# STM32_-_MCU.net
KiCad netlist of a schematic drawn in Altium Designer
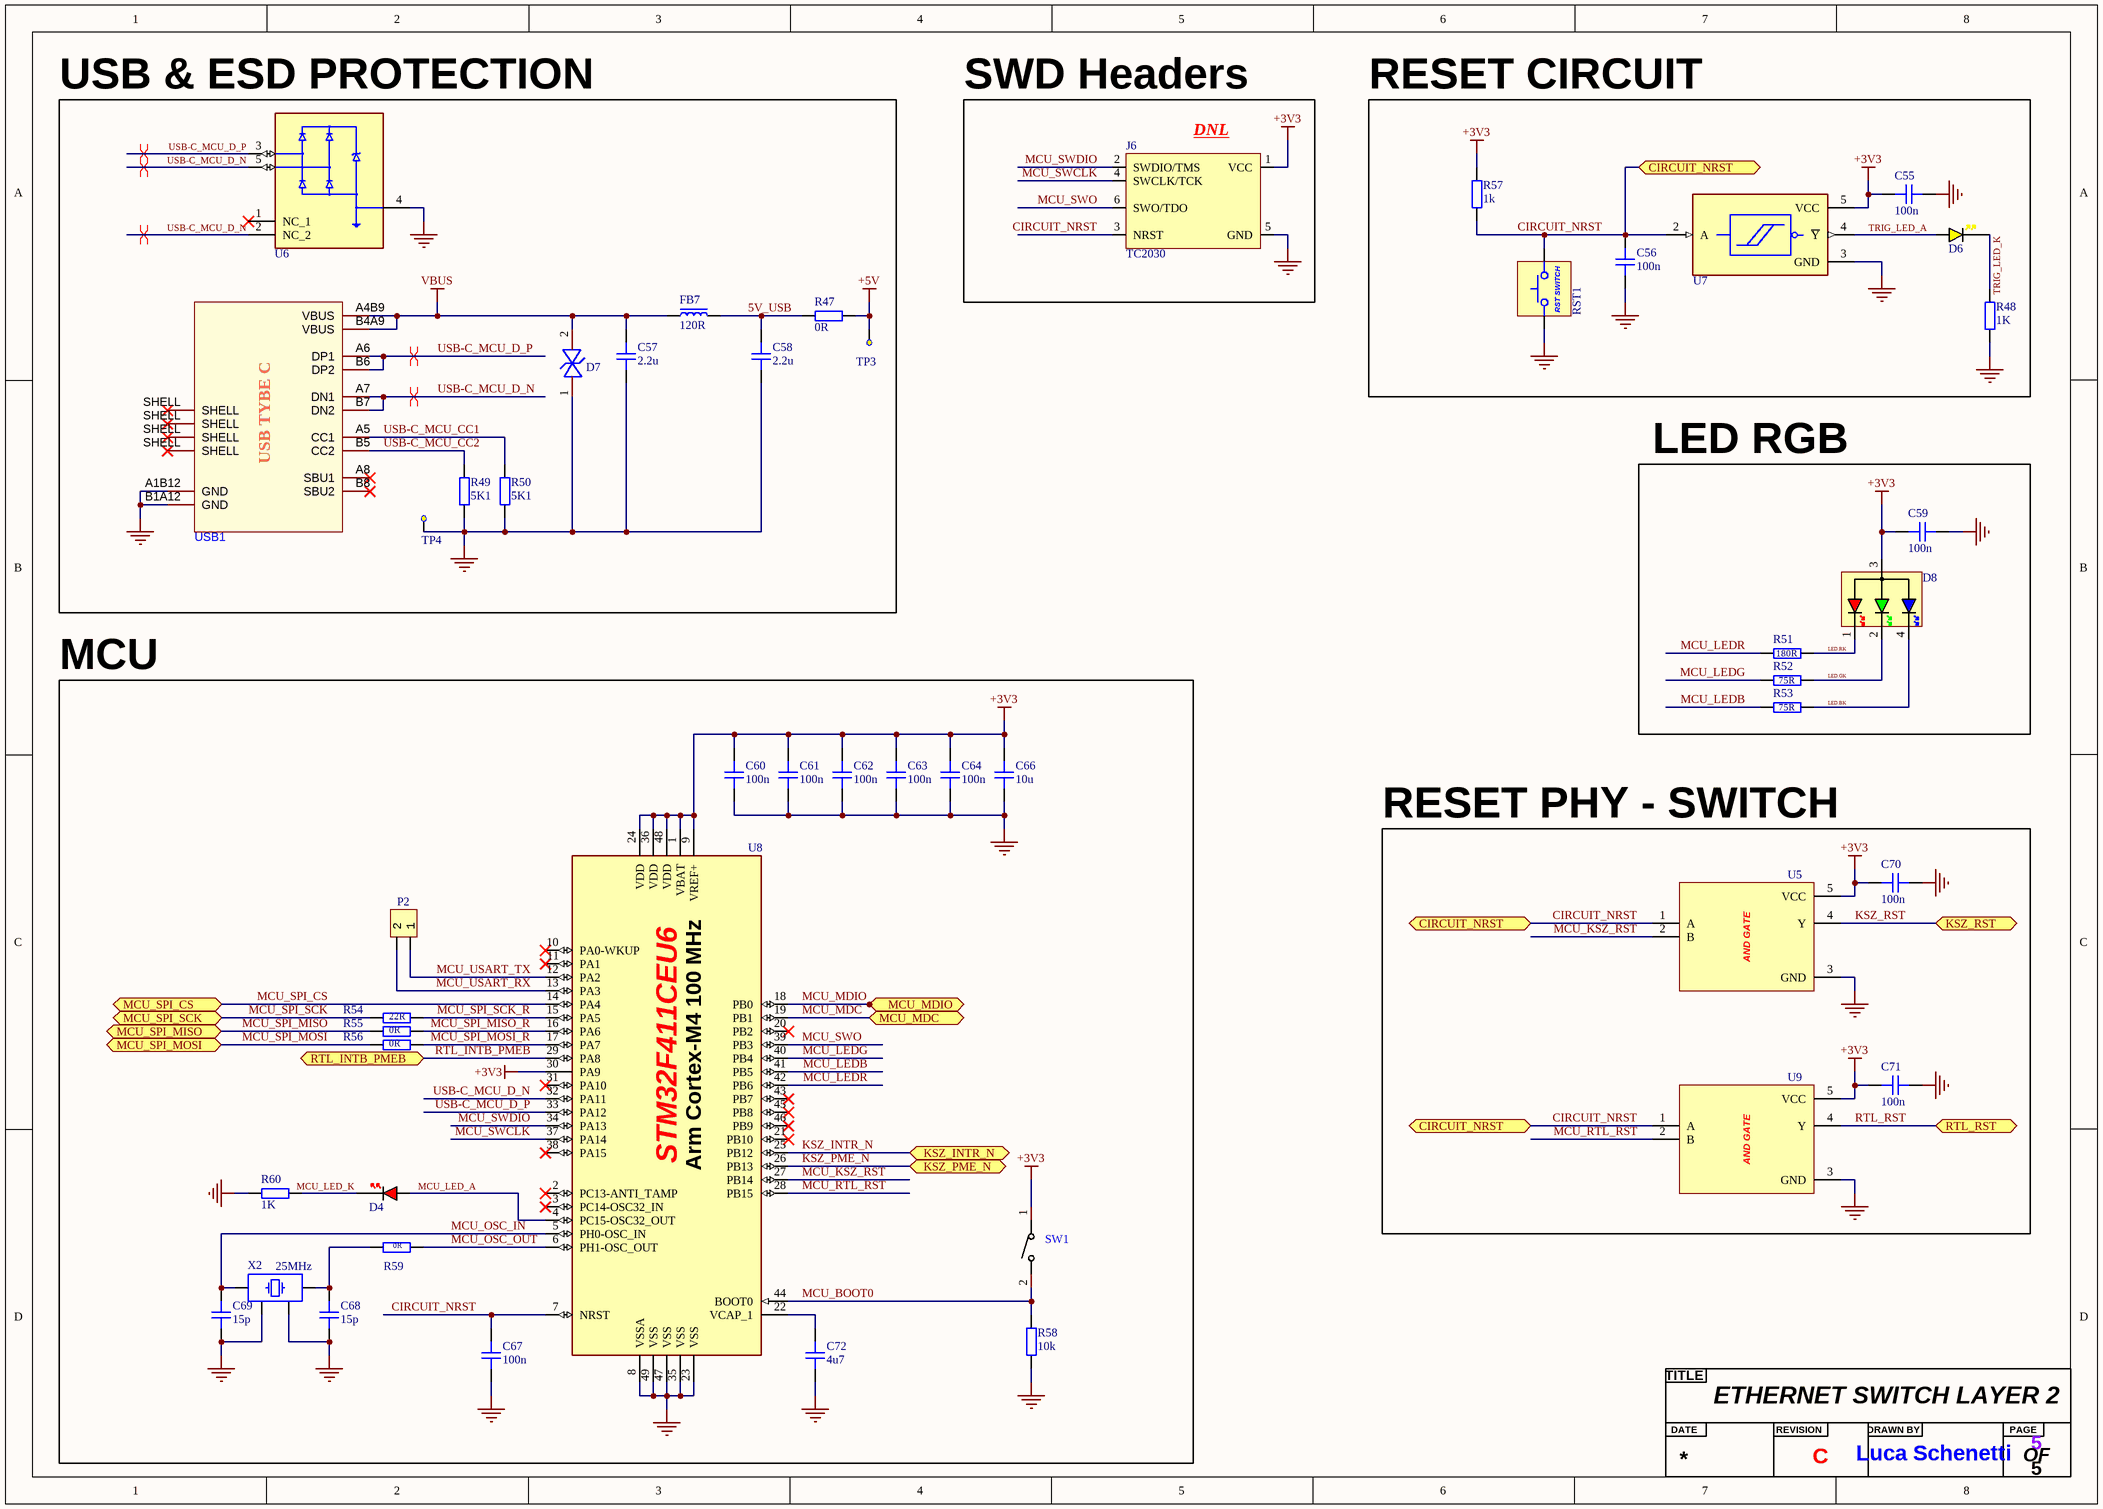
[diagram p0: STM32 - MCU.SchDoc]

(export (version "E")
  (design (tool "Eeschema 10.0.6"))
  (components
    (comp (ref "C55")
      (value "100n")
      (footprint "CAP_0402")
      (description "Capacitor SMD 0402 [C1525]")
      (libsource (lib "Schematic-Lib-PhilsLab") (part "CAP_0402"))
    )
    (comp (ref "C56")
      (value "100n")
      (footprint "CAP_0402")
      (description "Capacitor SMD 0402 [C1525]")
      (libsource (lib "Schematic-Lib-PhilsLab") (part "CAP_0402"))
    )
    (comp (ref "C57")
      (value "2.2u")
      (footprint "CAP_0603")
      (description "Capacitor SMD 0603 [C23630]")
      (libsource (lib "Schematic-Lib-PhilsLab") (part "CAP_0603"))
    )
    (comp (ref "C58")
      (value "2.2u")
      (footprint "CAP_0603")
      (description "Capacitor SMD 0603 [C23630]")
      (libsource (lib "Schematic-Lib-PhilsLab") (part "CAP_0603"))
    )
    (comp (ref "C59")
      (value "100n")
      (footprint "CAP_0402")
      (description "Capacitor SMD 0402 [C1525]")
      (libsource (lib "Schematic-Lib-PhilsLab") (part "CAP_0402"))
    )
    (comp (ref "C60")
      (value "100n")
      (footprint "CAP_0603")
      (description "Capacitor SMD 0603 [C14663]")
      (libsource (lib "Schematic-Lib-PhilsLab") (part "CAP_0603"))
    )
    (comp (ref "C61")
      (value "100n")
      (footprint "CAP_0603")
      (description "Capacitor SMD 0603 [C14663]")
      (libsource (lib "Schematic-Lib-PhilsLab") (part "CAP_0603"))
    )
    (comp (ref "C62")
      (value "100n")
      (footprint "CAP_0603")
      (description "Capacitor SMD 0603 [C14663]")
      (libsource (lib "Schematic-Lib-PhilsLab") (part "CAP_0603"))
    )
    (comp (ref "C63")
      (value "100n")
      (footprint "CAP_0603")
      (description "Capacitor SMD 0603 [C14663]")
      (libsource (lib "Schematic-Lib-PhilsLab") (part "CAP_0603"))
    )
    (comp (ref "C64")
      (value "100n")
      (footprint "CAP_0603")
      (description "Capacitor SMD 0603 [C14663]")
      (libsource (lib "Schematic-Lib-PhilsLab") (part "CAP_0603"))
    )
    (comp (ref "C66")
      (value "10u")
      (footprint "CAP_0603")
      (description "Capacitor SMD 0603 [C96446]")
      (libsource (lib "Schematic-Lib-PhilsLab") (part "CAP_0603"))
    )
    (comp (ref "C67")
      (value "100n")
      (footprint "CAP_0603")
      (description "Capacitor SMD 0603 [C14663]")
      (libsource (lib "Schematic-Lib-PhilsLab") (part "CAP_0603"))
    )
    (comp (ref "C68")
      (value "15p")
      (footprint "CAP_0402")
      (description "Capacitor SMD 0402 [C1548]")
      (libsource (lib "Schematic-Lib-PhilsLab") (part "CAP_0402"))
    )
    (comp (ref "C69")
      (value "15p")
      (footprint "CAP_0402")
      (description "Capacitor SMD 0402 [C1548]")
      (libsource (lib "Schematic-Lib-PhilsLab") (part "CAP_0402"))
    )
    (comp (ref "C70")
      (value "100n")
      (footprint "CAP_0402")
      (description "Capacitor SMD 0402 [C1525]")
      (libsource (lib "Schematic-Lib-PhilsLab") (part "CAP_0402"))
    )
    (comp (ref "C71")
      (value "100n")
      (footprint "CAP_0402")
      (description "Capacitor SMD 0402 [C1525]")
      (libsource (lib "Schematic-Lib-PhilsLab") (part "CAP_0402"))
    )
    (comp (ref "C72")
      (value "4u7")
      (footprint "CAP_0603")
      (description "Capacitor SMD 0603 [C19666]")
      (libsource (lib "Schematic-Lib-PhilsLab") (part "CAP_0603"))
    )
    (comp (ref "D4")
      (value "RED")
      (footprint "LED_0603_RED")
      (description "LED 0603 RED SMD[C2926776]")
      (libsource (lib "Schematic-Lib-PhilsLab") (part "LED_0603_RED"))
    )
    (comp (ref "D6")
      (value "YELLOW")
      (footprint "LED_0603_YELLOW")
      (description "LED 0603 YELLOW SMD[C72038]")
      (libsource (lib "Schematic-Lib-PhilsLab") (part "LED_0603_YELLOW"))
    )
    (comp (ref "D7")
      (value "ESD Protection TVS 6.0V")
      (footprint "SMF6.0CA")
      (description "[C2990473]")
      (libsource (lib "My_Library") (part "SMF6.0CA"))
    )
    (comp (ref "D8")
      (value "RGB_LED")
      (footprint "XL-2012RGBC")
      (description "[C965848]")
      (libsource (lib "My_Library") (part "RGB_LED_0805"))
    )
    (comp (ref "FB7")
      (value "120R")
      (footprint "FB_0603")
      (description "Ferrite Bead SMD 0603[C76892]")
      (libsource (lib "Schematic-Lib-PhilsLab") (part "FB_0603"))
    )
    (comp (ref "J6")
      (value "TC2030")
      (footprint "TC2030-FP")
      (description "Tag-Connect No-Solder SWD Debug Connector DO NOT PLACE")
      (fields (field (name "MANUFACTURER") "Tag-Connect"))
      (libsource (lib "Schematic-Lib-PhilsLab") (part "TC2030"))
    )
    (comp (ref "P2")
      (value "HDR1x2")
      (footprint "PCB_ConnectorHDR:HDR1X2_2.54_180")
      (description "Header")
      (libsource (lib "SCH_ConnectorHDR") (part "HDR1x2_2.54T"))
    )
    (comp (ref "R47")
      (value "0R")
      (footprint "RES_0603")
      (description "[C21189]")
      (libsource (lib "Schematic-Lib-PhilsLab") (part "RES_0603"))
    )
    (comp (ref "R48")
      (value "1K")
      (footprint "RES_0402")
      (description "Resistor SMD 0402 [C11702]")
      (libsource (lib "Schematic-Lib-PhilsLab") (part "RES_0402"))
    )
    (comp (ref "R49")
      (value "5K1")
      (footprint "RES_0603")
      (description "[C23186]")
      (libsource (lib "Schematic-Lib-PhilsLab") (part "RES_0603"))
    )
    (comp (ref "R50")
      (value "5K1")
      (footprint "RES_0603")
      (description "[C23186]")
      (libsource (lib "Schematic-Lib-PhilsLab") (part "RES_0603"))
    )
    (comp (ref "R51")
      (value "180R")
      (footprint "RES_0603")
      (description "[C22828]")
      (libsource (lib "Schematic-Lib-PhilsLab") (part "RES_0603"))
    )
    (comp (ref "R52")
      (value "75R")
      (footprint "RES_0603")
      (description "[C4275]")
      (libsource (lib "Schematic-Lib-PhilsLab") (part "RES_0603"))
    )
    (comp (ref "R53")
      (value "75R")
      (footprint "RES_0603")
      (description "[C4275]")
      (libsource (lib "Schematic-Lib-PhilsLab") (part "RES_0603"))
    )
    (comp (ref "R54")
      (value "22R")
      (footprint "RES_0402")
      (description "Resistor SMD 0402 [C25092]")
      (libsource (lib "Schematic-Lib-PhilsLab") (part "RES_0402"))
    )
    (comp (ref "R55")
      (value "0R")
      (footprint "RES_0402")
      (description "Resistor SMD 0402 [C17168]")
      (libsource (lib "Schematic-Lib-PhilsLab") (part "RES_0402"))
    )
    (comp (ref "R56")
      (value "0R")
      (footprint "RES_0402")
      (description "Resistor SMD 0402 [C17168]")
      (libsource (lib "Schematic-Lib-PhilsLab") (part "RES_0402"))
    )
    (comp (ref "R57")
      (value "1k")
      (footprint "RES_0402")
      (description "Resistor SMD 0402 [C11702]")
      (libsource (lib "Schematic-Lib-PhilsLab") (part "RES_0402"))
    )
    (comp (ref "R58")
      (value "10k")
      (footprint "RES_0603")
      (description "Resistor SMD 0603[C25804]")
      (libsource (lib "Schematic-Lib-PhilsLab") (part "RES_0603"))
    )
    (comp (ref "R59")
      (value "0R")
      (footprint "RES_0402")
      (description "Resistor SMD 0402 [C17168]")
      (libsource (lib "Schematic-Lib-PhilsLab") (part "RES_0402"))
    )
    (comp (ref "R60")
      (value "1K")
      (footprint "RES_0402")
      (description "Resistor SMD 0402 [C11702]")
      (libsource (lib "Schematic-Lib-PhilsLab") (part "RES_0402"))
    )
    (comp (ref "RST1")
      (value "RST_SWITCH_STM32")
      (footprint "RST_SWITCH")
      (description "[C720477]")
      (libsource (lib "My_Library") (part "RST_SWITCH"))
    )
    (comp (ref "SW1")
      (value "TS-1088-AR02016")
      (footprint "TS-1088-AR02016")
      (description "[C720477]")
      (fields (field (name "MANUFACTURER") "XUNPU(讯普)"))
      (libsource (lib "My_Library") (part "TS-1088-AR02016"))
    )
    (comp (ref "TP3")
      (value "Test Point")
      (footprint "Test Point")
      (libsource (lib "My_Library") (part "Test Point"))
    )
    (comp (ref "TP4")
      (value "Test Point")
      (footprint "Test Point")
      (libsource (lib "My_Library") (part "Test Point"))
    )
    (comp (ref "U5")
      (value "AND GATE")
      (footprint "SN74LVC1G08DBVR")
      (description "[C7666]")
      (libsource (lib "My_Library") (part "SN74LVC1G08DBVR"))
    )
    (comp (ref "U6")
      (value "TVS USB 2.0 ±25-kV")
      (footprint "TPD2E2U06DRLR")
      (description "[C1972959]")
      (libsource (lib "My_Library") (part "TPD2E2U06DRLR"))
    )
    (comp (ref "U7")
      (value "Schmitt Trigger 1.65V~5.5V")
      (footprint "74LVC1G14GW,125")
      (description "[C265125]")
      (libsource (lib "My_Library") (part "74LVC1G14GW,125"))
    )
    (comp (ref "U8")
      (value "ARM® Cortex®-M4 STM32F4")
      (footprint "STM32F411CEU6")
      (description "[C60420]")
      (libsource (lib "My_Library") (part "STM32F411CEU6"))
    )
    (comp (ref "U9")
      (value "AND GATE")
      (footprint "SN74LVC1G08DBVR")
      (description "[C7666]")
      (libsource (lib "My_Library") (part "SN74LVC1G08DBVR"))
    )
    (comp (ref "USB1")
      (value "USB-C CONNECTOR")
      (footprint "USB-3.1-SMD_U262-161N-4BVC11")
      (description "[C319148]")
      (fields
        (field (name "MANUFACTURER") "XKB Connectivity(中国星坤)")
        (field (name "MANUFACTURER PART") "U262-161N-4BVC11")
      )
      (libsource (lib "My_Library") (part "U262-161N-4BVC11"))
    )
    (comp (ref "X2")
      (value "25MHz")
      (footprint "XTAL_3225")
      (description "Crystal SMD 24MHz 10PPM 7pF 3225 [C9006]")
      (fields
        (field (name "MANUFACTURER") "Epson")
        (field (name "MANUFACTURER PART NUMBER") "TSX-3225 24.0000MF15X-AC")
      )
      (libsource (lib "Schematic-Lib-PhilsLab") (part "TSX-3225_24.0000MF15X-AC"))
    )
  )
  (nets
    (net (code "1") (name "+3V3") (class "Default")
      (node (ref "C55") (pin "2") (pinfunction "2_2") (pintype "passive"))
      (node (ref "C59") (pin "2") (pinfunction "2_2") (pintype "passive"))
      (node (ref "C60") (pin "2") (pinfunction "2_2") (pintype "passive"))
      (node (ref "C61") (pin "2") (pinfunction "2_2") (pintype "passive"))
      (node (ref "C62") (pin "2") (pinfunction "2_2") (pintype "passive"))
      (node (ref "C63") (pin "2") (pinfunction "2_2") (pintype "passive"))
      (node (ref "C64") (pin "2") (pinfunction "2_2") (pintype "passive"))
      (node (ref "C66") (pin "2") (pinfunction "2_2") (pintype "passive"))
      (node (ref "C70") (pin "2") (pinfunction "2_2") (pintype "passive"))
      (node (ref "C71") (pin "2") (pinfunction "2_2") (pintype "passive"))
      (node (ref "D8") (pin "3") (pinfunction "AC_3") (pintype "passive"))
      (node (ref "J6") (pin "1") (pinfunction "VCC_1") (pintype "passive"))
      (node (ref "R57") (pin "2") (pinfunction "2_2") (pintype "passive"))
      (node (ref "SW1") (pin "1") (pinfunction "1_1") (pintype "passive"))
      (node (ref "U5") (pin "5") (pinfunction "VCC_5") (pintype "power_in"))
      (node (ref "U7") (pin "5") (pinfunction "VCC_5") (pintype "power_in"))
      (node (ref "U8") (pin "1") (pinfunction "VBAT_1") (pintype "power_in"))
      (node (ref "U8") (pin "24") (pinfunction "VDD_24") (pintype "power_in"))
      (node (ref "U8") (pin "30") (pinfunction "PA9_30") (pintype "passive"))
      (node (ref "U8") (pin "36") (pinfunction "VDD_36") (pintype "power_in"))
      (node (ref "U8") (pin "48") (pinfunction "VDD_48") (pintype "power_in"))
      (node (ref "U8") (pin "9") (pinfunction "VREF+_9") (pintype "power_in"))
      (node (ref "U9") (pin "5") (pinfunction "VCC_5") (pintype "power_in"))
    )
    (net (code "2") (name "+5V") (class "Default")
      (node (ref "R47") (pin "2") (pinfunction "2_2") (pintype "passive"))
      (node (ref "TP3") (pin "1") (pinfunction "Test_Point_1") (pintype "passive"))
    )
    (net (code "3") (name "/5V_USB") (class "Default")
      (node (ref "C58") (pin "2") (pinfunction "2_2") (pintype "passive"))
      (node (ref "FB7") (pin "2") (pinfunction "2_2") (pintype "passive"))
      (node (ref "R47") (pin "1") (pinfunction "1_1") (pintype "passive"))
    )
    (net (code "4") (name "/CIRCUIT_NRST") (class "Default")
      (node (ref "C56") (pin "2") (pinfunction "2_2") (pintype "passive"))
      (node (ref "C67") (pin "2") (pinfunction "2_2") (pintype "passive"))
      (node (ref "J6") (pin "3") (pinfunction "NRST_3") (pintype "passive"))
      (node (ref "R57") (pin "1") (pinfunction "1_1") (pintype "passive"))
      (node (ref "RST1") (pin "2") (pintype "passive"))
      (node (ref "U5") (pin "1") (pinfunction "A_1") (pintype "passive"))
      (node (ref "U7") (pin "2") (pinfunction "A_2") (pintype "input"))
      (node (ref "U8") (pin "7") (pinfunction "NRST_7") (pintype "bidirectional"))
      (node (ref "U9") (pin "1") (pinfunction "A_1") (pintype "passive"))
    )
    (net (code "5") (name "/KSZ_INTR_N") (class "Default")
      (node (ref "U8") (pin "25") (pinfunction "PB12_25") (pintype "bidirectional"))
    )
    (net (code "6") (name "/KSZ_PME_N") (class "Default")
      (node (ref "U8") (pin "26") (pinfunction "PB13_26") (pintype "bidirectional"))
    )
    (net (code "7") (name "/KSZ_RST") (class "Default")
      (node (ref "U5") (pin "4") (pinfunction "Y_4") (pintype "passive"))
    )
    (net (code "8") (name "/LED.BK") (class "Default")
      (node (ref "D8") (pin "4") (pinfunction "CB_4") (pintype "passive"))
      (node (ref "R53") (pin "1") (pinfunction "1_1") (pintype "passive"))
    )
    (net (code "9") (name "/LED.GK") (class "Default")
      (node (ref "D8") (pin "2") (pinfunction "CG_2") (pintype "passive"))
      (node (ref "R52") (pin "1") (pinfunction "1_1") (pintype "passive"))
    )
    (net (code "10") (name "/LED.RK") (class "Default")
      (node (ref "D8") (pin "1") (pinfunction "CR_1") (pintype "passive"))
      (node (ref "R51") (pin "1") (pinfunction "1_1") (pintype "passive"))
    )
    (net (code "11") (name "/MCU_BOOT0") (class "Default")
      (node (ref "R58") (pin "2") (pinfunction "2_2") (pintype "passive"))
      (node (ref "SW1") (pin "2") (pinfunction "2_2") (pintype "passive"))
      (node (ref "U8") (pin "44") (pinfunction "BOOT0_44") (pintype "input"))
    )
    (net (code "12") (name "/MCU_KSZ_RST") (class "Default")
      (node (ref "U5") (pin "2") (pinfunction "B_2") (pintype "passive"))
      (node (ref "U8") (pin "27") (pinfunction "PB14_27") (pintype "bidirectional"))
    )
    (net (code "13") (name "/MCU_LEDB") (class "Default")
      (node (ref "R53") (pin "2") (pinfunction "2_2") (pintype "passive"))
      (node (ref "U8") (pin "41") (pinfunction "PB5_41") (pintype "bidirectional"))
    )
    (net (code "14") (name "/MCU_LEDG") (class "Default")
      (node (ref "R52") (pin "2") (pinfunction "2_2") (pintype "passive"))
      (node (ref "U8") (pin "40") (pinfunction "PB4_40") (pintype "bidirectional"))
    )
    (net (code "15") (name "/MCU_LEDR") (class "Default")
      (node (ref "R51") (pin "2") (pinfunction "2_2") (pintype "passive"))
      (node (ref "U8") (pin "42") (pinfunction "PB6_42") (pintype "bidirectional"))
    )
    (net (code "16") (name "/MCU_LED_A") (class "Default")
      (node (ref "D4") (pin "A") (pinfunction "A_A") (pintype "passive"))
      (node (ref "U8") (pin "4") (pinfunction "PC15-OSC32_OUT_4") (pintype "bidirectional"))
    )
    (net (code "17") (name "/MCU_LED_K") (class "Default")
      (node (ref "D4") (pin "K") (pinfunction "K_K") (pintype "passive"))
      (node (ref "R60") (pin "2") (pinfunction "2_2") (pintype "passive"))
    )
    (net (code "18") (name "/MCU_MDC") (class "Default")
      (node (ref "U8") (pin "19") (pinfunction "PB1_19") (pintype "bidirectional"))
    )
    (net (code "19") (name "/MCU_MDIO") (class "Default")
      (node (ref "U8") (pin "18") (pinfunction "PB0_18") (pintype "bidirectional"))
    )
    (net (code "20") (name "/MCU_OSC_IN") (class "Default")
      (node (ref "C69") (pin "2") (pinfunction "2_2") (pintype "passive"))
      (node (ref "U8") (pin "5") (pinfunction "PH0-OSC_IN_5") (pintype "bidirectional"))
      (node (ref "X2") (pin "3") (pinfunction "3_3") (pintype "passive"))
    )
    (net (code "21") (name "/MCU_OSC_OUT") (class "Default")
      (node (ref "R59") (pin "2") (pinfunction "2_2") (pintype "passive"))
      (node (ref "U8") (pin "6") (pinfunction "PH1-OSC_OUT_6") (pintype "bidirectional"))
    )
    (net (code "22") (name "/MCU_RTL_RST") (class "Default")
      (node (ref "U8") (pin "28") (pinfunction "PB15_28") (pintype "bidirectional"))
      (node (ref "U9") (pin "2") (pinfunction "B_2") (pintype "passive"))
    )
    (net (code "23") (name "/MCU_SPI_CS") (class "Default")
      (node (ref "U8") (pin "14") (pinfunction "PA4_14") (pintype "bidirectional"))
    )
    (net (code "24") (name "/MCU_SPI_MISO") (class "Default")
      (node (ref "R55") (pin "1") (pinfunction "1_1") (pintype "passive"))
    )
    (net (code "25") (name "/MCU_SPI_MISO_R") (class "Default")
      (node (ref "R55") (pin "2") (pinfunction "2_2") (pintype "passive"))
      (node (ref "U8") (pin "16") (pinfunction "PA6_16") (pintype "bidirectional"))
    )
    (net (code "26") (name "/MCU_SPI_MOSI") (class "Default")
      (node (ref "R56") (pin "1") (pinfunction "1_1") (pintype "passive"))
    )
    (net (code "27") (name "/MCU_SPI_MOSI_R") (class "Default")
      (node (ref "R56") (pin "2") (pinfunction "2_2") (pintype "passive"))
      (node (ref "U8") (pin "17") (pinfunction "PA7_17") (pintype "bidirectional"))
    )
    (net (code "28") (name "/MCU_SPI_SCK") (class "Default")
      (node (ref "R54") (pin "1") (pinfunction "1_1") (pintype "passive"))
    )
    (net (code "29") (name "/MCU_SPI_SCK_R") (class "Default")
      (node (ref "R54") (pin "2") (pinfunction "2_2") (pintype "passive"))
      (node (ref "U8") (pin "15") (pinfunction "PA5_15") (pintype "bidirectional"))
    )
    (net (code "30") (name "/MCU_SWCLK") (class "Default")
      (node (ref "J6") (pin "4") (pinfunction "SWCLK/TCK_4") (pintype "passive"))
      (node (ref "U8") (pin "37") (pinfunction "PA14_37") (pintype "bidirectional"))
    )
    (net (code "31") (name "/MCU_SWDIO") (class "Default")
      (node (ref "J6") (pin "2") (pinfunction "SWDIO/TMS_2") (pintype "passive"))
      (node (ref "U8") (pin "34") (pinfunction "PA13_34") (pintype "bidirectional"))
    )
    (net (code "32") (name "/MCU_SWO") (class "Default")
      (node (ref "J6") (pin "6") (pinfunction "SWO/TDO_6") (pintype "passive"))
      (node (ref "U8") (pin "39") (pinfunction "PB3_39") (pintype "bidirectional"))
    )
    (net (code "33") (name "/MCU_USART_RX") (class "Default")
      (node (ref "P2") (pin "2") (pinfunction "2_2") (pintype "passive"))
      (node (ref "U8") (pin "13") (pinfunction "PA3_13") (pintype "bidirectional"))
    )
    (net (code "34") (name "/MCU_USART_TX") (class "Default")
      (node (ref "P2") (pin "1") (pinfunction "1_1") (pintype "passive"))
      (node (ref "U8") (pin "12") (pinfunction "PA2_12") (pintype "bidirectional"))
    )
    (net (code "35") (name "/RTL_INTB_PMEB") (class "Default")
      (node (ref "U8") (pin "29") (pinfunction "PA8_29") (pintype "bidirectional"))
    )
    (net (code "36") (name "/RTL_RST") (class "Default")
      (node (ref "U9") (pin "4") (pinfunction "Y_4") (pintype "passive"))
    )
    (net (code "37") (name "/TRIG_LED_A") (class "Default")
      (node (ref "D6") (pin "A") (pinfunction "A_A") (pintype "passive"))
      (node (ref "U7") (pin "4") (pinfunction "~{Y}_4") (pintype "output"))
    )
    (net (code "38") (name "/TRIG_LED_K") (class "Default")
      (node (ref "D6") (pin "K") (pinfunction "K_K") (pintype "passive"))
      (node (ref "R48") (pin "2") (pinfunction "2_2") (pintype "passive"))
    )
    (net (code "39") (name "/USB-C_MCU_CC1") (class "Default")
      (node (ref "R50") (pin "2") (pinfunction "2_2") (pintype "passive"))
      (node (ref "USB1") (pin "A5") (pinfunction "CC1_A5") (pintype "passive"))
    )
    (net (code "40") (name "/USB-C_MCU_CC2") (class "Default")
      (node (ref "R49") (pin "2") (pinfunction "2_2") (pintype "passive"))
      (node (ref "USB1") (pin "B5") (pinfunction "CC2_B5") (pintype "passive"))
    )
    (net (code "41") (name "/USB-C_MCU_D_N") (class "Default")
      (node (ref "U6") (pin "2") (pinfunction "NC_2_2") (pintype "passive"))
      (node (ref "U6") (pin "5") (pinfunction "IO2_5") (pintype "bidirectional"))
      (node (ref "U8") (pin "32") (pinfunction "PA11_32") (pintype "bidirectional"))
      (node (ref "USB1") (pin "A7") (pinfunction "DN1_A7") (pintype "passive"))
      (node (ref "USB1") (pin "B7") (pinfunction "DN2_B7") (pintype "passive"))
    )
    (net (code "42") (name "/USB-C_MCU_D_P") (class "Default")
      (node (ref "U6") (pin "3") (pinfunction "IO1_3") (pintype "bidirectional"))
      (node (ref "U8") (pin "33") (pinfunction "PA12_33") (pintype "bidirectional"))
      (node (ref "USB1") (pin "A6") (pinfunction "DP1_A6") (pintype "passive"))
      (node (ref "USB1") (pin "B6") (pinfunction "DP2_B6") (pintype "passive"))
    )
    (net (code "43") (name "GND") (class "Default")
      (node (ref "C55") (pin "1") (pinfunction "1_1") (pintype "passive"))
      (node (ref "C56") (pin "1") (pinfunction "1_1") (pintype "passive"))
      (node (ref "C57") (pin "1") (pinfunction "1_1") (pintype "passive"))
      (node (ref "C58") (pin "1") (pinfunction "1_1") (pintype "passive"))
      (node (ref "C59") (pin "1") (pinfunction "1_1") (pintype "passive"))
      (node (ref "C60") (pin "1") (pinfunction "1_1") (pintype "passive"))
      (node (ref "C61") (pin "1") (pinfunction "1_1") (pintype "passive"))
      (node (ref "C62") (pin "1") (pinfunction "1_1") (pintype "passive"))
      (node (ref "C63") (pin "1") (pinfunction "1_1") (pintype "passive"))
      (node (ref "C64") (pin "1") (pinfunction "1_1") (pintype "passive"))
      (node (ref "C66") (pin "1") (pinfunction "1_1") (pintype "passive"))
      (node (ref "C67") (pin "1") (pinfunction "1_1") (pintype "passive"))
      (node (ref "C68") (pin "1") (pinfunction "1_1") (pintype "passive"))
      (node (ref "C69") (pin "1") (pinfunction "1_1") (pintype "passive"))
      (node (ref "C70") (pin "1") (pinfunction "1_1") (pintype "passive"))
      (node (ref "C71") (pin "1") (pinfunction "1_1") (pintype "passive"))
      (node (ref "C72") (pin "1") (pinfunction "1_1") (pintype "passive"))
      (node (ref "D7") (pin "1") (pinfunction "C_1") (pintype "passive"))
      (node (ref "J6") (pin "5") (pinfunction "GND_5") (pintype "passive"))
      (node (ref "R48") (pin "1") (pinfunction "1_1") (pintype "passive"))
      (node (ref "R49") (pin "1") (pinfunction "1_1") (pintype "passive"))
      (node (ref "R50") (pin "1") (pinfunction "1_1") (pintype "passive"))
      (node (ref "R58") (pin "1") (pinfunction "1_1") (pintype "passive"))
      (node (ref "R60") (pin "1") (pinfunction "1_1") (pintype "passive"))
      (node (ref "RST1") (pin "1") (pintype "passive"))
      (node (ref "TP4") (pin "1") (pinfunction "Test_Point_1") (pintype "passive"))
      (node (ref "U5") (pin "3") (pinfunction "GND_3") (pintype "power_in"))
      (node (ref "U6") (pin "4") (pinfunction "GND_4") (pintype "power_in"))
      (node (ref "U7") (pin "3") (pinfunction "GND_3") (pintype "power_in"))
      (node (ref "U8") (pin "23") (pinfunction "VSS_23") (pintype "power_in"))
      (node (ref "U8") (pin "35") (pinfunction "VSS_35") (pintype "power_in"))
      (node (ref "U8") (pin "47") (pinfunction "VSS_47") (pintype "power_in"))
      (node (ref "U8") (pin "49") (pinfunction "VSS_49") (pintype "power_in"))
      (node (ref "U8") (pin "8") (pinfunction "VSSA_8") (pintype "power_in"))
      (node (ref "U9") (pin "3") (pinfunction "GND_3") (pintype "power_in"))
      (node (ref "USB1") (pin "A1B12") (pinfunction "GND_A1B12") (pintype "passive"))
      (node (ref "USB1") (pin "B1A12") (pinfunction "GND_B1A12") (pintype "passive"))
      (node (ref "X2") (pin "2") (pinfunction "2_2") (pintype "passive"))
      (node (ref "X2") (pin "4") (pinfunction "4_4") (pintype "passive"))
    )
    (net (code "44") (name "Net-(C68-Pad2)") (class "Default")
      (node (ref "C68") (pin "2") (pinfunction "2_2") (pintype "passive"))
      (node (ref "R59") (pin "1") (pinfunction "1_1") (pintype "passive"))
      (node (ref "X2") (pin "1") (pinfunction "1_1") (pintype "passive"))
    )
    (net (code "45") (name "Net-(U8-VCAP_1)") (class "Default")
      (node (ref "C72") (pin "2") (pinfunction "2_2") (pintype "passive"))
      (node (ref "U8") (pin "22") (pinfunction "VCAP_1_22") (pintype "power_in"))
    )
    (net (code "46") (name "VBUS") (class "Default")
      (node (ref "C57") (pin "2") (pinfunction "2_2") (pintype "passive"))
      (node (ref "D7") (pin "2") (pinfunction "A_2") (pintype "passive"))
      (node (ref "FB7") (pin "1") (pinfunction "1_1") (pintype "passive"))
      (node (ref "USB1") (pin "A4B9") (pinfunction "VBUS_A4B9") (pintype "passive"))
      (node (ref "USB1") (pin "B4A9") (pinfunction "VBUS_B4A9") (pintype "passive"))
    )
    (net (code "47") (name "unconnected-(U6-NC_1-Pad1)") (class "Default")
      (node (ref "U6") (pin "1") (pinfunction "NC_1_1") (pintype "passive+no_connect"))
    )
    (net (code "48") (name "unconnected-(U8-PA0-WKUP-Pad10)") (class "Default")
      (node (ref "U8") (pin "10") (pinfunction "PA0-WKUP_10") (pintype "bidirectional+no_connect"))
    )
    (net (code "49") (name "unconnected-(U8-PA1-Pad11)") (class "Default")
      (node (ref "U8") (pin "11") (pinfunction "PA1_11") (pintype "bidirectional+no_connect"))
    )
    (net (code "50") (name "unconnected-(U8-PA10-Pad31)") (class "Default")
      (node (ref "U8") (pin "31") (pinfunction "PA10_31") (pintype "bidirectional+no_connect"))
    )
    (net (code "51") (name "unconnected-(U8-PA15-Pad38)") (class "Default")
      (node (ref "U8") (pin "38") (pinfunction "PA15_38") (pintype "bidirectional+no_connect"))
    )
    (net (code "52") (name "unconnected-(U8-PB2-Pad20)") (class "Default")
      (node (ref "U8") (pin "20") (pinfunction "PB2_20") (pintype "bidirectional+no_connect"))
    )
    (net (code "53") (name "unconnected-(U8-PB7-Pad43)") (class "Default")
      (node (ref "U8") (pin "43") (pinfunction "PB7_43") (pintype "bidirectional+no_connect"))
    )
    (net (code "54") (name "unconnected-(U8-PB8-Pad45)") (class "Default")
      (node (ref "U8") (pin "45") (pinfunction "PB8_45") (pintype "bidirectional+no_connect"))
    )
    (net (code "55") (name "unconnected-(U8-PB9-Pad46)") (class "Default")
      (node (ref "U8") (pin "46") (pinfunction "PB9_46") (pintype "bidirectional+no_connect"))
    )
    (net (code "56") (name "unconnected-(U8-PB10-Pad21)") (class "Default")
      (node (ref "U8") (pin "21") (pinfunction "PB10_21") (pintype "bidirectional+no_connect"))
    )
    (net (code "57") (name "unconnected-(U8-PC13-ANTI_TAMP-Pad2)") (class "Default")
      (node (ref "U8") (pin "2") (pinfunction "PC13-ANTI_TAMP_2") (pintype "bidirectional+no_connect"))
    )
    (net (code "58") (name "unconnected-(U8-PC14-OSC32_IN-Pad3)") (class "Default")
      (node (ref "U8") (pin "3") (pinfunction "PC14-OSC32_IN_3") (pintype "bidirectional+no_connect"))
    )
    (net (code "59") (name "unconnected-(USB1-PadSHELL)") (class "Default")
      (node (ref "USB1") (pin "SHELL") (pinfunction "SHELL_SHELL") (pintype "passive+no_connect"))
    )
    (net (code "60") (name "unconnected-(USB1-PadSHELL)_1") (class "Default")
      (node (ref "USB1") (pin "SHELL") (pinfunction "SHELL_SHELL") (pintype "passive+no_connect"))
    )
    (net (code "61") (name "unconnected-(USB1-PadSHELL)_2") (class "Default")
      (node (ref "USB1") (pin "SHELL") (pinfunction "SHELL_SHELL") (pintype "passive+no_connect"))
    )
    (net (code "62") (name "unconnected-(USB1-PadSHELL)_3") (class "Default")
      (node (ref "USB1") (pin "SHELL") (pinfunction "SHELL_SHELL") (pintype "passive+no_connect"))
    )
    (net (code "63") (name "unconnected-(USB1-SBU1-PadA8)") (class "Default")
      (node (ref "USB1") (pin "A8") (pinfunction "SBU1_A8") (pintype "passive+no_connect"))
    )
    (net (code "64") (name "unconnected-(USB1-SBU2-PadB8)") (class "Default")
      (node (ref "USB1") (pin "B8") (pinfunction "SBU2_B8") (pintype "passive+no_connect"))
    )
  )
)
